# PROC010B_DUT_Reference.net
KiCad netlist of a schematic drawn in Altium Designer
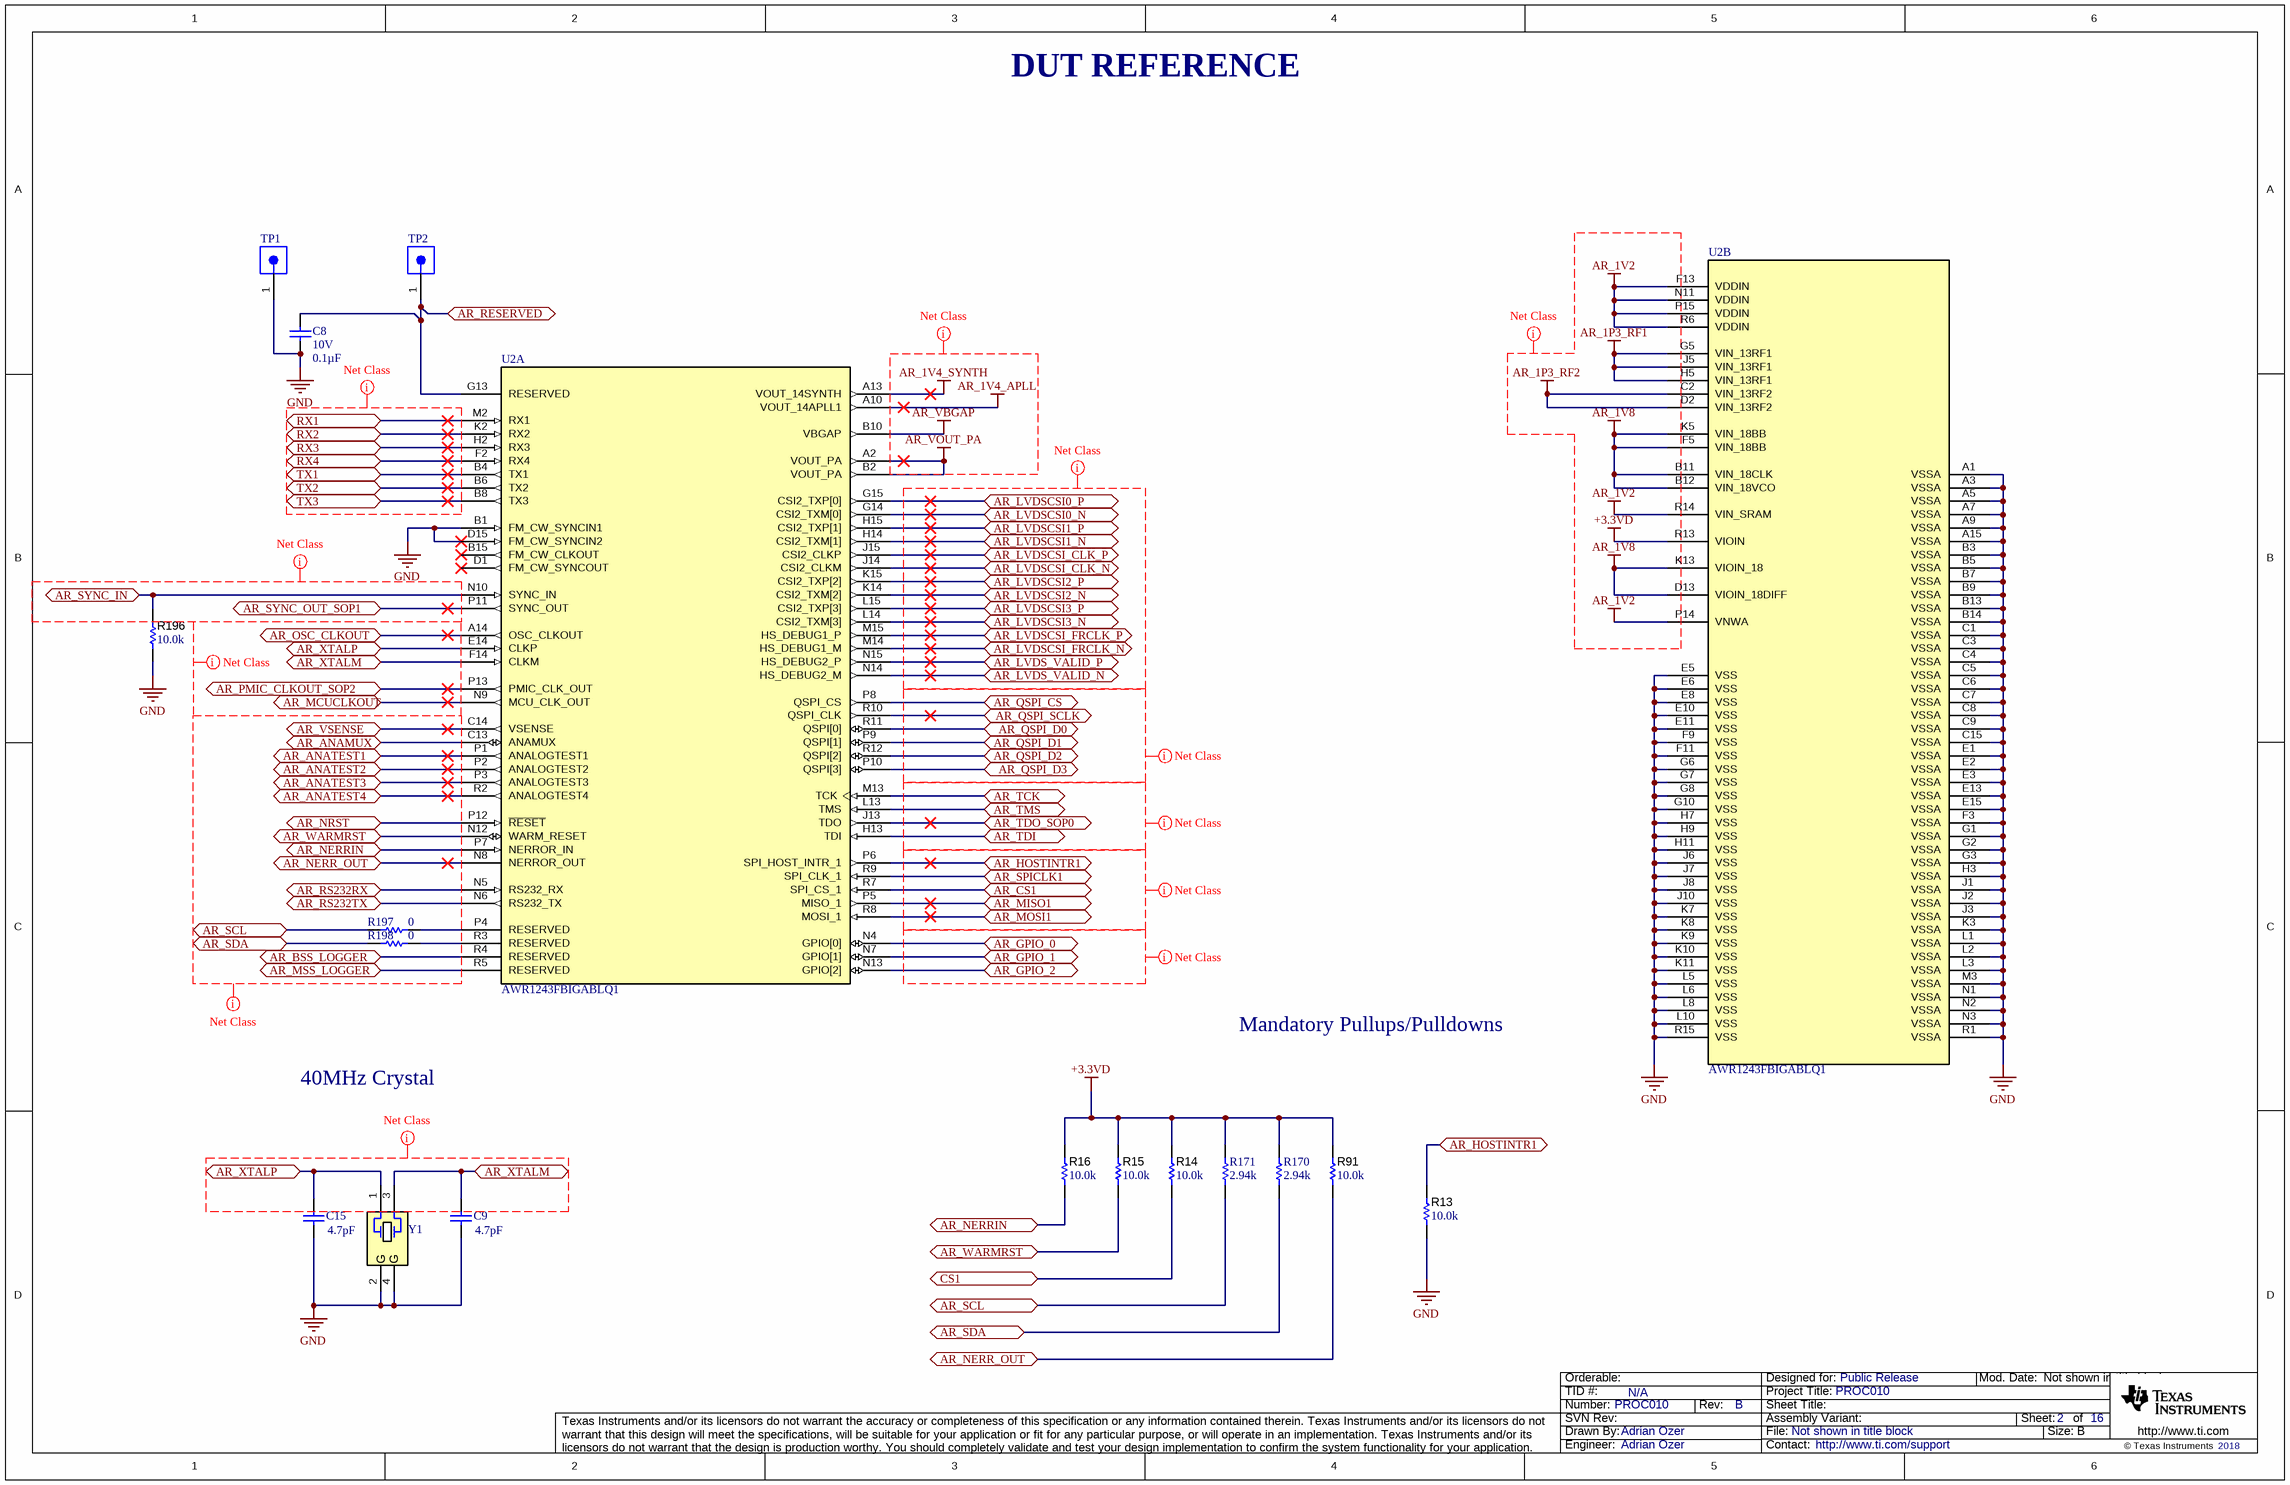
[diagram p0: PROC010B_DUT_Reference.SchDoc]

(export (version "E")
  (design (tool "Eeschema 10.0.6"))
  (components
    (comp (ref "C8")
      (value "C0603X7S1A104K030BC")
      (footprint "0201_033")
      (description "CAP, CERM, 0.1 µF, 10 V,+/- 10%, X7S, 0201")
      (fields
        (field (name "MANUFACTURER") "TDK")
        (field (name "VDC_V") "10V")
        (field (name "VALUEDISPLAYED") "0.1µF")
      )
      (libsource (lib "Altium Vault - TI") (part "Capacitor"))
    )
    (comp (ref "C9")
      (value "GJM1555C1H4R7BB01D")
      (footprint "0402")
      (description "CAP, CERM, 4.7 pF, 50 V, +/- 2%, C0G/NP0, 0402")
      (fields
        (field (name "MANUFACTURER") "MuRata")
        (field (name "VALUEDISPLAYED") "4.7pF")
        (field (name "PUBLISHER") "Texas Instruments")
      )
      (libsource (lib "Altium Vault - TI") (part "CMP-0006367-2"))
    )
    (comp (ref "C15")
      (value "GJM1555C1H4R7BB01D")
      (footprint "0402")
      (description "CAP, CERM, 4.7 pF, 50 V, +/- 2%, C0G/NP0, 0402")
      (fields
        (field (name "MANUFACTURER") "MuRata")
        (field (name "VALUEDISPLAYED") "4.7pF")
        (field (name "PUBLISHER") "Texas Instruments")
      )
      (libsource (lib "Altium Vault - TI") (part "CMP-0006367-2"))
    )
    (comp (ref "R13")
      (value "CRCW040210K0FKED")
      (footprint "0402L")
      (description "RES, 10.0 k, 1%, 0.063 W, AEC-Q200 Grade 0, 0402")
      (fields (field (name "MANUFACTURER") "Vishay-Dale") (field (name "VALUEDISPLAYED") "10.0k"))
      (libsource (lib "Altium Vault - TI") (part "Resistor"))
    )
    (comp (ref "R14")
      (value "CRCW040210K0FKED")
      (footprint "0402L")
      (description "RES, 10.0 k, 1%, 0.063 W, AEC-Q200 Grade 0, 0402")
      (fields (field (name "MANUFACTURER") "Vishay-Dale") (field (name "VALUEDISPLAYED") "10.0k"))
      (libsource (lib "Altium Vault - TI") (part "Resistor"))
    )
    (comp (ref "R15")
      (value "CRCW040210K0FKED")
      (footprint "0402L")
      (description "RES, 10.0 k, 1%, 0.063 W, AEC-Q200 Grade 0, 0402")
      (fields (field (name "MANUFACTURER") "Vishay-Dale") (field (name "VALUEDISPLAYED") "10.0k"))
      (libsource (lib "Altium Vault - TI") (part "Resistor"))
    )
    (comp (ref "R16")
      (value "CRCW040210K0FKED")
      (footprint "0402L")
      (description "RES, 10.0 k, 1%, 0.063 W, AEC-Q200 Grade 0, 0402")
      (fields (field (name "MANUFACTURER") "Vishay-Dale") (field (name "VALUEDISPLAYED") "10.0k"))
      (libsource (lib "Altium Vault - TI") (part "Resistor"))
    )
    (comp (ref "R91")
      (value "CRCW040210K0FKED")
      (footprint "0402L")
      (description "RES, 10.0 k, 1%, 0.063 W, AEC-Q200 Grade 0, 0402")
      (fields (field (name "MANUFACTURER") "Vishay-Dale") (field (name "VALUEDISPLAYED") "10.0k"))
      (libsource (lib "Altium Vault - TI") (part "Resistor"))
    )
    (comp (ref "R170")
      (value "CRCW04022K94FKED")
      (footprint "0402")
      (description "RES, 2.94 k, 1%, 0.063 W, AEC-Q200 Grade 0, 0402")
      (fields (field (name "MANUFACTURER") "Vishay-Dale") (field (name "VALUEDISPLAYED") "2.94k"))
      (libsource (lib "Altium Vault - TI") (part "Resistor"))
    )
    (comp (ref "R171")
      (value "CRCW04022K94FKED")
      (footprint "0402")
      (description "RES, 2.94 k, 1%, 0.063 W, AEC-Q200 Grade 0, 0402")
      (fields (field (name "MANUFACTURER") "Vishay-Dale") (field (name "VALUEDISPLAYED") "2.94k"))
      (libsource (lib "Altium Vault - TI") (part "Resistor"))
    )
    (comp (ref "R196")
      (value "CRCW040210K0FKED")
      (footprint "0402L")
      (description "RES, 10.0 k, 1%, 0.063 W, AEC-Q200 Grade 0, 0402")
      (fields (field (name "MANUFACTURER") "Vishay-Dale") (field (name "VALUEDISPLAYED") "10.0k"))
      (libsource (lib "Altium Vault - TI") (part "CMP-0025958-3"))
    )
    (comp (ref "R197")
      (value "CRCW02010000Z0ED")
      (footprint "0201")
      (description "RES, 0, 5%, 0.05 W, 0201")
      (fields (field (name "MANUFACTURER") "Vishay-Dale") (field (name "VALUEDISPLAYED") "0"))
      (libsource (lib "Altium Vault - TI") (part "Resistor"))
    )
    (comp (ref "R198")
      (value "CRCW02010000Z0ED")
      (footprint "0201")
      (description "RES, 0, 5%, 0.05 W, 0201")
      (fields (field (name "MANUFACTURER") "Vishay-Dale") (field (name "VALUEDISPLAYED") "0"))
      (libsource (lib "Altium Vault - TI") (part "Resistor"))
    )
    (comp (ref "TP1")
      (value "TSW-101-17-T-S")
      (footprint "Samtec_TSW-101-17-T-S")
      (description "Header, 100mil, 1x1, Tin, TH")
      (fields (field (name "MANUFACTURER") "Samtec") (field (name "PUBLISHER") "Texas Instruments"))
      (libsource (lib "Altium Vault - TI") (part "Header_1x1"))
    )
    (comp (ref "TP2")
      (value "TSW-101-17-T-S")
      (footprint "Samtec_TSW-101-17-T-S")
      (description "Header, 100mil, 1x1, Tin, TH")
      (fields (field (name "MANUFACTURER") "Samtec") (field (name "PUBLISHER") "Texas Instruments"))
      (libsource (lib "Altium Vault - TI") (part "Header_1x1"))
    )
    (comp (ref "U2")
      (value "AWR1243FBIGABLQ1")
      (footprint "ABL0161A")
      (description "Single Chip 77 and 79 GHz FMCW Transceiver, ABL0161A (FCBGA-161)")
      (fields
        (field (name "ALTERNATE PARTNUMBER") "AWR1243FBIGABLRQ1")
        (field (name "MANUFACTURER") "Texas Instruments")
        (field (name "PARTNUMBER") "AWR1243FBIGABLQ1")
      )
      (libsource (lib "Altium Vault - TI") (part "CMP-0081285-1"))
    )
    (comp (ref "Y1")
      (value "CX3225SA40000D0PTWCC")
      (footprint "Kyocera_CX3225SA")
      (description "Crystal, 40 MHz, 8pF, SMD")
      (fields (field (name "MANUFACTURER") "Kyocera"))
      (libsource (lib "Altium Vault - TI") (part "XTAL_4P_13_24OPEN"))
    )
  )
  (nets
    (net (code "1") (name "+3.3VD") (class "Default")
      (node (ref "R14") (pin "2") (pinfunction "2_2") (pintype "passive"))
      (node (ref "R15") (pin "2") (pinfunction "2_2") (pintype "passive"))
      (node (ref "R16") (pin "2") (pinfunction "2_2") (pintype "passive"))
      (node (ref "R170") (pin "2") (pinfunction "2_2") (pintype "passive"))
      (node (ref "R171") (pin "2") (pinfunction "2_2") (pintype "passive"))
      (node (ref "R91") (pin "2") (pinfunction "2_2") (pintype "passive"))
      (node (ref "U2") (pin "R13") (pinfunction "VIOIN_R13") (pintype "power_in"))
    )
    (net (code "2") (name "/AR_ANAMUX") (class "Default")
      (node (ref "U2") (pin "C13") (pinfunction "ANAMUX_C13") (pintype "bidirectional"))
    )
    (net (code "3") (name "/AR_ANATEST1") (class "Default")
      (node (ref "U2") (pin "P1") (pinfunction "ANALOGTEST1_P1") (pintype "output"))
    )
    (net (code "4") (name "/AR_ANATEST2") (class "Default")
      (node (ref "U2") (pin "P2") (pinfunction "ANALOGTEST2_P2") (pintype "output"))
    )
    (net (code "5") (name "/AR_ANATEST3") (class "Default")
      (node (ref "U2") (pin "P3") (pinfunction "ANALOGTEST3_P3") (pintype "output"))
    )
    (net (code "6") (name "/AR_ANATEST4") (class "Default")
      (node (ref "U2") (pin "R2") (pinfunction "ANALOGTEST4_R2") (pintype "output"))
    )
    (net (code "7") (name "/AR_BSS_LOGGER") (class "Default")
      (node (ref "U2") (pin "R4") (pinfunction "RESERVED_R4") (pintype "passive"))
    )
    (net (code "8") (name "/AR_CS1") (class "Default")
      (node (ref "U2") (pin "R7") (pinfunction "SPI_CS_1_R7") (pintype "input"))
    )
    (net (code "9") (name "/AR_GPIO_0") (class "Default")
      (node (ref "U2") (pin "N4") (pinfunction "GPIO[0]_N4") (pintype "bidirectional"))
    )
    (net (code "10") (name "/AR_GPIO_1") (class "Default")
      (node (ref "U2") (pin "N7") (pinfunction "GPIO[1]_N7") (pintype "bidirectional"))
    )
    (net (code "11") (name "/AR_GPIO_2") (class "Default")
      (node (ref "U2") (pin "N13") (pinfunction "GPIO[2]_N13") (pintype "bidirectional"))
    )
    (net (code "12") (name "/AR_HOSTINTR1") (class "Default")
      (node (ref "R13") (pin "2") (pinfunction "2_2") (pintype "passive"))
      (node (ref "U2") (pin "P6") (pinfunction "SPI_HOST_INTR_1_P6") (pintype "output"))
    )
    (net (code "13") (name "/AR_LVDSCSI0_N") (class "Default")
      (node (ref "U2") (pin "G14") (pinfunction "CSI2_TXM[0]_G14") (pintype "output"))
    )
    (net (code "14") (name "/AR_LVDSCSI0_P") (class "Default")
      (node (ref "U2") (pin "G15") (pinfunction "CSI2_TXP[0]_G15") (pintype "output"))
    )
    (net (code "15") (name "/AR_LVDSCSI1_N") (class "Default")
      (node (ref "U2") (pin "H14") (pinfunction "CSI2_TXM[1]_H14") (pintype "output"))
    )
    (net (code "16") (name "/AR_LVDSCSI1_P") (class "Default")
      (node (ref "U2") (pin "H15") (pinfunction "CSI2_TXP[1]_H15") (pintype "output"))
    )
    (net (code "17") (name "/AR_LVDSCSI2_N") (class "Default")
      (node (ref "U2") (pin "K14") (pinfunction "CSI2_TXM[2]_K14") (pintype "output"))
    )
    (net (code "18") (name "/AR_LVDSCSI2_P") (class "Default")
      (node (ref "U2") (pin "K15") (pinfunction "CSI2_TXP[2]_K15") (pintype "output"))
    )
    (net (code "19") (name "/AR_LVDSCSI3_N") (class "Default")
      (node (ref "U2") (pin "L14") (pinfunction "CSI2_TXM[3]_L14") (pintype "output"))
    )
    (net (code "20") (name "/AR_LVDSCSI3_P") (class "Default")
      (node (ref "U2") (pin "L15") (pinfunction "CSI2_TXP[3]_L15") (pintype "output"))
    )
    (net (code "21") (name "/AR_LVDSCSI_CLK_N") (class "Default")
      (node (ref "U2") (pin "J14") (pinfunction "CSI2_CLKM_J14") (pintype "output"))
    )
    (net (code "22") (name "/AR_LVDSCSI_CLK_P") (class "Default")
      (node (ref "U2") (pin "J15") (pinfunction "CSI2_CLKP_J15") (pintype "output"))
    )
    (net (code "23") (name "/AR_LVDSCSI_FRCLK_N") (class "Default")
      (node (ref "U2") (pin "M14") (pinfunction "HS_DEBUG1_M_M14") (pintype "output"))
    )
    (net (code "24") (name "/AR_LVDSCSI_FRCLK_P") (class "Default")
      (node (ref "U2") (pin "M15") (pinfunction "HS_DEBUG1_P_M15") (pintype "output"))
    )
    (net (code "25") (name "/AR_LVDS_VALID_N") (class "Default")
      (node (ref "U2") (pin "N14") (pinfunction "HS_DEBUG2_M_N14") (pintype "output"))
    )
    (net (code "26") (name "/AR_LVDS_VALID_P") (class "Default")
      (node (ref "U2") (pin "N15") (pinfunction "HS_DEBUG2_P_N15") (pintype "output"))
    )
    (net (code "27") (name "/AR_MCUCLKOUT") (class "Default")
      (node (ref "U2") (pin "N9") (pinfunction "MCU_CLK_OUT_N9") (pintype "output"))
    )
    (net (code "28") (name "/AR_MISO1") (class "Default")
      (node (ref "U2") (pin "P5") (pinfunction "MISO_1_P5") (pintype "output"))
    )
    (net (code "29") (name "/AR_MOSI1") (class "Default")
      (node (ref "U2") (pin "R8") (pinfunction "MOSI_1_R8") (pintype "input"))
    )
    (net (code "30") (name "/AR_MSS_LOGGER") (class "Default")
      (node (ref "U2") (pin "R5") (pinfunction "RESERVED_R5") (pintype "passive"))
    )
    (net (code "31") (name "/AR_NERRIN") (class "Default")
      (node (ref "R16") (pin "1") (pinfunction "1_1") (pintype "passive"))
      (node (ref "U2") (pin "P7") (pinfunction "NERROR_IN_P7") (pintype "input"))
    )
    (net (code "32") (name "/AR_NERR_OUT") (class "Default")
      (node (ref "R91") (pin "1") (pinfunction "1_1") (pintype "passive"))
      (node (ref "U2") (pin "N8") (pinfunction "NERROR_OUT_N8") (pintype "open_collector"))
    )
    (net (code "33") (name "/AR_NRST") (class "Default")
      (node (ref "U2") (pin "P12") (pinfunction "RESET_P12") (pintype "input"))
    )
    (net (code "34") (name "/AR_OSC_CLKOUT") (class "Default")
      (node (ref "U2") (pin "A14") (pinfunction "OSC_CLKOUT_A14") (pintype "output"))
    )
    (net (code "35") (name "/AR_PMIC_CLKOUT_SOP2") (class "Default")
      (node (ref "U2") (pin "P13") (pinfunction "PMIC_CLK_OUT_P13") (pintype "output"))
    )
    (net (code "36") (name "/AR_QSPI_CS") (class "Default")
      (node (ref "U2") (pin "P8") (pinfunction "QSPI_CS_P8") (pintype "output"))
    )
    (net (code "37") (name "/AR_QSPI_D0") (class "Default")
      (node (ref "U2") (pin "R11") (pinfunction "QSPI[0]_R11") (pintype "bidirectional"))
    )
    (net (code "38") (name "/AR_QSPI_D1") (class "Default")
      (node (ref "U2") (pin "P9") (pinfunction "QSPI[1]_P9") (pintype "bidirectional"))
    )
    (net (code "39") (name "/AR_QSPI_D2") (class "Default")
      (node (ref "U2") (pin "R12") (pinfunction "QSPI[2]_R12") (pintype "bidirectional"))
    )
    (net (code "40") (name "/AR_QSPI_D3") (class "Default")
      (node (ref "U2") (pin "P10") (pinfunction "QSPI[3]_P10") (pintype "bidirectional"))
    )
    (net (code "41") (name "/AR_QSPI_SCLK") (class "Default")
      (node (ref "U2") (pin "R10") (pinfunction "QSPI_CLK_R10") (pintype "output"))
    )
    (net (code "42") (name "/AR_RESERVED") (class "Default")
      (node (ref "C8") (pin "1") (pinfunction "1_1") (pintype "passive"))
      (node (ref "TP2") (pin "1") (pinfunction "1_1") (pintype "passive"))
      (node (ref "U2") (pin "G13") (pinfunction "RESERVED_G13") (pintype "power_in"))
    )
    (net (code "43") (name "/AR_RS232RX") (class "Default")
      (node (ref "U2") (pin "N5") (pinfunction "RS232_RX_N5") (pintype "input"))
    )
    (net (code "44") (name "/AR_RS232TX") (class "Default")
      (node (ref "U2") (pin "N6") (pinfunction "RS232_TX_N6") (pintype "output"))
    )
    (net (code "45") (name "/AR_SCL") (class "Default")
      (node (ref "R171") (pin "1") (pinfunction "1_1") (pintype "passive"))
      (node (ref "R197") (pin "1") (pinfunction "1_1") (pintype "passive"))
    )
    (net (code "46") (name "/AR_SDA") (class "Default")
      (node (ref "R170") (pin "1") (pinfunction "1_1") (pintype "passive"))
      (node (ref "R198") (pin "1") (pinfunction "1_1") (pintype "passive"))
    )
    (net (code "47") (name "/AR_SPICLK1") (class "Default")
      (node (ref "U2") (pin "R9") (pinfunction "SPI_CLK_1_R9") (pintype "input"))
    )
    (net (code "48") (name "/AR_SYNC_IN") (class "Default")
      (node (ref "R196") (pin "2") (pinfunction "2_2") (pintype "passive"))
      (node (ref "U2") (pin "N10") (pinfunction "SYNC_IN_N10") (pintype "input"))
    )
    (net (code "49") (name "/AR_SYNC_OUT_SOP1") (class "Default")
      (node (ref "U2") (pin "P11") (pinfunction "SYNC_OUT_P11") (pintype "output"))
    )
    (net (code "50") (name "/AR_TCK") (class "Default")
      (node (ref "U2") (pin "M13") (pinfunction "TCK_M13") (pintype "input"))
    )
    (net (code "51") (name "/AR_TDI") (class "Default")
      (node (ref "U2") (pin "H13") (pinfunction "TDI_H13") (pintype "input"))
    )
    (net (code "52") (name "/AR_TDO_SOP0") (class "Default")
      (node (ref "U2") (pin "J13") (pinfunction "TDO_J13") (pintype "output"))
    )
    (net (code "53") (name "/AR_TMS") (class "Default")
      (node (ref "U2") (pin "L13") (pinfunction "TMS_L13") (pintype "input"))
    )
    (net (code "54") (name "/AR_VSENSE") (class "Default")
      (node (ref "U2") (pin "C14") (pinfunction "VSENSE_C14") (pintype "output"))
    )
    (net (code "55") (name "/AR_WARMRST") (class "Default")
      (node (ref "R15") (pin "1") (pinfunction "1_1") (pintype "passive"))
      (node (ref "U2") (pin "N12") (pinfunction "WARM_RESET_N12") (pintype "bidirectional"))
    )
    (net (code "56") (name "/AR_XTALM") (class "Default")
      (node (ref "C9") (pin "1") (pinfunction "1_1") (pintype "passive"))
      (node (ref "U2") (pin "F14") (pinfunction "CLKM_F14") (pintype "input"))
      (node (ref "Y1") (pin "3") (pinfunction "3_3") (pintype "passive"))
    )
    (net (code "57") (name "/AR_XTALP") (class "Default")
      (node (ref "C15") (pin "2") (pinfunction "2_2") (pintype "passive"))
      (node (ref "U2") (pin "E14") (pinfunction "CLKP_E14") (pintype "input"))
      (node (ref "Y1") (pin "1") (pinfunction "1_1") (pintype "passive"))
    )
    (net (code "58") (name "/CS1") (class "Default")
      (node (ref "R14") (pin "1") (pinfunction "1_1") (pintype "passive"))
    )
    (net (code "59") (name "/RX1") (class "Default")
      (node (ref "U2") (pin "M2") (pinfunction "RX1_M2") (pintype "input"))
    )
    (net (code "60") (name "/RX2") (class "Default")
      (node (ref "U2") (pin "K2") (pinfunction "RX2_K2") (pintype "input"))
    )
    (net (code "61") (name "/RX3") (class "Default")
      (node (ref "U2") (pin "H2") (pinfunction "RX3_H2") (pintype "input"))
    )
    (net (code "62") (name "/RX4") (class "Default")
      (node (ref "U2") (pin "F2") (pinfunction "RX4_F2") (pintype "input"))
    )
    (net (code "63") (name "/TX1") (class "Default")
      (node (ref "U2") (pin "B4") (pinfunction "TX1_B4") (pintype "output"))
    )
    (net (code "64") (name "/TX2") (class "Default")
      (node (ref "U2") (pin "B6") (pinfunction "TX2_B6") (pintype "output"))
    )
    (net (code "65") (name "/TX3") (class "Default")
      (node (ref "U2") (pin "B8") (pinfunction "TX3_B8") (pintype "output"))
    )
    (net (code "66") (name "AR_1P3_RF1") (class "Default")
      (node (ref "U2") (pin "G5") (pinfunction "VIN_13RF1_G5") (pintype "power_in"))
      (node (ref "U2") (pin "H5") (pinfunction "VIN_13RF1_H5") (pintype "power_in"))
      (node (ref "U2") (pin "J5") (pinfunction "VIN_13RF1_J5") (pintype "power_in"))
    )
    (net (code "67") (name "AR_1P3_RF2") (class "Default")
      (node (ref "U2") (pin "C2") (pinfunction "VIN_13RF2_C2") (pintype "power_in"))
      (node (ref "U2") (pin "D2") (pinfunction "VIN_13RF2_D2") (pintype "power_in"))
    )
    (net (code "68") (name "AR_1V2") (class "Default")
      (node (ref "U2") (pin "F13") (pinfunction "VDDIN_F13") (pintype "power_in"))
      (node (ref "U2") (pin "N11") (pinfunction "VDDIN_N11") (pintype "power_in"))
      (node (ref "U2") (pin "P14") (pinfunction "VNWA_P14") (pintype "power_in"))
      (node (ref "U2") (pin "P15") (pinfunction "VDDIN_P15") (pintype "power_in"))
      (node (ref "U2") (pin "R14") (pinfunction "VIN_SRAM_R14") (pintype "power_in"))
      (node (ref "U2") (pin "R6") (pinfunction "VDDIN_R6") (pintype "power_in"))
    )
    (net (code "69") (name "AR_1V4_APLL") (class "Default")
      (node (ref "U2") (pin "A10") (pinfunction "VOUT_14APLL1_A10") (pintype "output"))
    )
    (net (code "70") (name "AR_1V4_SYNTH") (class "Default")
      (node (ref "U2") (pin "A13") (pinfunction "VOUT_14SYNTH_A13") (pintype "output"))
    )
    (net (code "71") (name "AR_1V8") (class "Default")
      (node (ref "U2") (pin "B11") (pinfunction "VIN_18CLK_B11") (pintype "power_in"))
      (node (ref "U2") (pin "B12") (pinfunction "VIN_18VCO_B12") (pintype "power_in"))
      (node (ref "U2") (pin "D13") (pinfunction "VIOIN_18DIFF_D13") (pintype "power_in"))
      (node (ref "U2") (pin "F5") (pinfunction "VIN_18BB_F5") (pintype "power_in"))
      (node (ref "U2") (pin "K13") (pinfunction "VIOIN_18_K13") (pintype "power_in"))
      (node (ref "U2") (pin "K5") (pinfunction "VIN_18BB_K5") (pintype "power_in"))
    )
    (net (code "72") (name "AR_VBGAP") (class "Default")
      (node (ref "U2") (pin "B10") (pinfunction "VBGAP_B10") (pintype "output"))
    )
    (net (code "73") (name "AR_VOUT_PA") (class "Default")
      (node (ref "U2") (pin "A2") (pinfunction "VOUT_PA_A2") (pintype "output"))
      (node (ref "U2") (pin "B2") (pinfunction "VOUT_PA_B2") (pintype "output"))
    )
    (net (code "74") (name "GND") (class "Default")
      (node (ref "C15") (pin "1") (pinfunction "1_1") (pintype "passive"))
      (node (ref "C8") (pin "2") (pinfunction "2_2") (pintype "passive"))
      (node (ref "C9") (pin "2") (pinfunction "2_2") (pintype "passive"))
      (node (ref "R13") (pin "1") (pinfunction "1_1") (pintype "passive"))
      (node (ref "R196") (pin "1") (pinfunction "1_1") (pintype "passive"))
      (node (ref "TP1") (pin "1") (pinfunction "1_1") (pintype "passive"))
      (node (ref "U2") (pin "A1") (pinfunction "VSSA_A1") (pintype "power_in"))
      (node (ref "U2") (pin "A15") (pinfunction "VSSA_A15") (pintype "power_in"))
      (node (ref "U2") (pin "A3") (pinfunction "VSSA_A3") (pintype "power_in"))
      (node (ref "U2") (pin "A5") (pinfunction "VSSA_A5") (pintype "power_in"))
      (node (ref "U2") (pin "A7") (pinfunction "VSSA_A7") (pintype "power_in"))
      (node (ref "U2") (pin "A9") (pinfunction "VSSA_A9") (pintype "power_in"))
      (node (ref "U2") (pin "B1") (pinfunction "FM_CW_SYNCIN1_B1") (pintype "input"))
      (node (ref "U2") (pin "B13") (pinfunction "VSSA_B13") (pintype "power_in"))
      (node (ref "U2") (pin "B14") (pinfunction "VSSA_B14") (pintype "power_in"))
      (node (ref "U2") (pin "B3") (pinfunction "VSSA_B3") (pintype "power_in"))
      (node (ref "U2") (pin "B5") (pinfunction "VSSA_B5") (pintype "power_in"))
      (node (ref "U2") (pin "B7") (pinfunction "VSSA_B7") (pintype "power_in"))
      (node (ref "U2") (pin "B9") (pinfunction "VSSA_B9") (pintype "power_in"))
      (node (ref "U2") (pin "C1") (pinfunction "VSSA_C1") (pintype "power_in"))
      (node (ref "U2") (pin "C15") (pinfunction "VSSA_C15") (pintype "power_in"))
      (node (ref "U2") (pin "C3") (pinfunction "VSSA_C3") (pintype "power_in"))
      (node (ref "U2") (pin "C4") (pinfunction "VSSA_C4") (pintype "power_in"))
      (node (ref "U2") (pin "C5") (pinfunction "VSSA_C5") (pintype "power_in"))
      (node (ref "U2") (pin "C6") (pinfunction "VSSA_C6") (pintype "power_in"))
      (node (ref "U2") (pin "C7") (pinfunction "VSSA_C7") (pintype "power_in"))
      (node (ref "U2") (pin "C8") (pinfunction "VSSA_C8") (pintype "power_in"))
      (node (ref "U2") (pin "C9") (pinfunction "VSSA_C9") (pintype "power_in"))
      (node (ref "U2") (pin "D15") (pinfunction "FM_CW_SYNCIN2_D15") (pintype "input"))
      (node (ref "U2") (pin "E1") (pinfunction "VSSA_E1") (pintype "power_in"))
      (node (ref "U2") (pin "E10") (pinfunction "VSS_E10") (pintype "power_in"))
      (node (ref "U2") (pin "E11") (pinfunction "VSS_E11") (pintype "power_in"))
      (node (ref "U2") (pin "E13") (pinfunction "VSSA_E13") (pintype "power_in"))
      (node (ref "U2") (pin "E15") (pinfunction "VSSA_E15") (pintype "power_in"))
      (node (ref "U2") (pin "E2") (pinfunction "VSSA_E2") (pintype "power_in"))
      (node (ref "U2") (pin "E3") (pinfunction "VSSA_E3") (pintype "power_in"))
      (node (ref "U2") (pin "E5") (pinfunction "VSS_E5") (pintype "power_in"))
      (node (ref "U2") (pin "E6") (pinfunction "VSS_E6") (pintype "power_in"))
      (node (ref "U2") (pin "E8") (pinfunction "VSS_E8") (pintype "power_in"))
      (node (ref "U2") (pin "F11") (pinfunction "VSS_F11") (pintype "power_in"))
      (node (ref "U2") (pin "F3") (pinfunction "VSSA_F3") (pintype "power_in"))
      (node (ref "U2") (pin "F9") (pinfunction "VSS_F9") (pintype "power_in"))
      (node (ref "U2") (pin "G1") (pinfunction "VSSA_G1") (pintype "power_in"))
      (node (ref "U2") (pin "G10") (pinfunction "VSS_G10") (pintype "power_in"))
      (node (ref "U2") (pin "G2") (pinfunction "VSSA_G2") (pintype "power_in"))
      (node (ref "U2") (pin "G3") (pinfunction "VSSA_G3") (pintype "power_in"))
      (node (ref "U2") (pin "G6") (pinfunction "VSS_G6") (pintype "power_in"))
      (node (ref "U2") (pin "G7") (pinfunction "VSS_G7") (pintype "power_in"))
      (node (ref "U2") (pin "G8") (pinfunction "VSS_G8") (pintype "power_in"))
      (node (ref "U2") (pin "H11") (pinfunction "VSS_H11") (pintype "power_in"))
      (node (ref "U2") (pin "H3") (pinfunction "VSSA_H3") (pintype "power_in"))
      (node (ref "U2") (pin "H7") (pinfunction "VSS_H7") (pintype "power_in"))
      (node (ref "U2") (pin "H9") (pinfunction "VSS_H9") (pintype "power_in"))
      (node (ref "U2") (pin "J1") (pinfunction "VSSA_J1") (pintype "power_in"))
      (node (ref "U2") (pin "J10") (pinfunction "VSS_J10") (pintype "power_in"))
      (node (ref "U2") (pin "J2") (pinfunction "VSSA_J2") (pintype "power_in"))
      (node (ref "U2") (pin "J3") (pinfunction "VSSA_J3") (pintype "power_in"))
      (node (ref "U2") (pin "J6") (pinfunction "VSS_J6") (pintype "power_in"))
      (node (ref "U2") (pin "J7") (pinfunction "VSS_J7") (pintype "power_in"))
      (node (ref "U2") (pin "J8") (pinfunction "VSS_J8") (pintype "power_in"))
      (node (ref "U2") (pin "K10") (pinfunction "VSS_K10") (pintype "power_in"))
      (node (ref "U2") (pin "K11") (pinfunction "VSS_K11") (pintype "power_in"))
      (node (ref "U2") (pin "K3") (pinfunction "VSSA_K3") (pintype "power_in"))
      (node (ref "U2") (pin "K7") (pinfunction "VSS_K7") (pintype "power_in"))
      (node (ref "U2") (pin "K8") (pinfunction "VSS_K8") (pintype "power_in"))
      (node (ref "U2") (pin "K9") (pinfunction "VSS_K9") (pintype "power_in"))
      (node (ref "U2") (pin "L1") (pinfunction "VSSA_L1") (pintype "power_in"))
      (node (ref "U2") (pin "L10") (pinfunction "VSS_L10") (pintype "power_in"))
      (node (ref "U2") (pin "L2") (pinfunction "VSSA_L2") (pintype "power_in"))
      (node (ref "U2") (pin "L3") (pinfunction "VSSA_L3") (pintype "power_in"))
      (node (ref "U2") (pin "L5") (pinfunction "VSS_L5") (pintype "power_in"))
      (node (ref "U2") (pin "L6") (pinfunction "VSS_L6") (pintype "power_in"))
      (node (ref "U2") (pin "L8") (pinfunction "VSS_L8") (pintype "power_in"))
      (node (ref "U2") (pin "M3") (pinfunction "VSSA_M3") (pintype "power_in"))
      (node (ref "U2") (pin "N1") (pinfunction "VSSA_N1") (pintype "power_in"))
      (node (ref "U2") (pin "N2") (pinfunction "VSSA_N2") (pintype "power_in"))
      (node (ref "U2") (pin "N3") (pinfunction "VSSA_N3") (pintype "power_in"))
      (node (ref "U2") (pin "R1") (pinfunction "VSSA_R1") (pintype "power_in"))
      (node (ref "U2") (pin "R15") (pinfunction "VSS_R15") (pintype "power_in"))
      (node (ref "Y1") (pin "2") (pinfunction "GND_2") (pintype "power_in"))
      (node (ref "Y1") (pin "4") (pinfunction "GND_4") (pintype "power_in"))
    )
    (net (code "75") (name "Net-(R197-Pad2)") (class "Default")
      (node (ref "R197") (pin "2") (pinfunction "2_2") (pintype "passive"))
      (node (ref "U2") (pin "P4") (pinfunction "RESERVED_P4") (pintype "passive"))
    )
    (net (code "76") (name "Net-(R198-Pad2)") (class "Default")
      (node (ref "R198") (pin "2") (pinfunction "2_2") (pintype "passive"))
      (node (ref "U2") (pin "R3") (pinfunction "RESERVED_R3") (pintype "passive"))
    )
    (net (code "77") (name "unconnected-(U2A-FM_CW_CLKOUT-PadB15)") (class "Default")
      (node (ref "U2") (pin "B15") (pinfunction "FM_CW_CLKOUT_B15") (pintype "output+no_connect"))
    )
    (net (code "78") (name "unconnected-(U2A-FM_CW_SYNCOUT-PadD1)") (class "Default")
      (node (ref "U2") (pin "D1") (pinfunction "FM_CW_SYNCOUT_D1") (pintype "output+no_connect"))
    )
  )
)
